# trigger.net
KiCad netlist of a schematic drawn in EAGLE
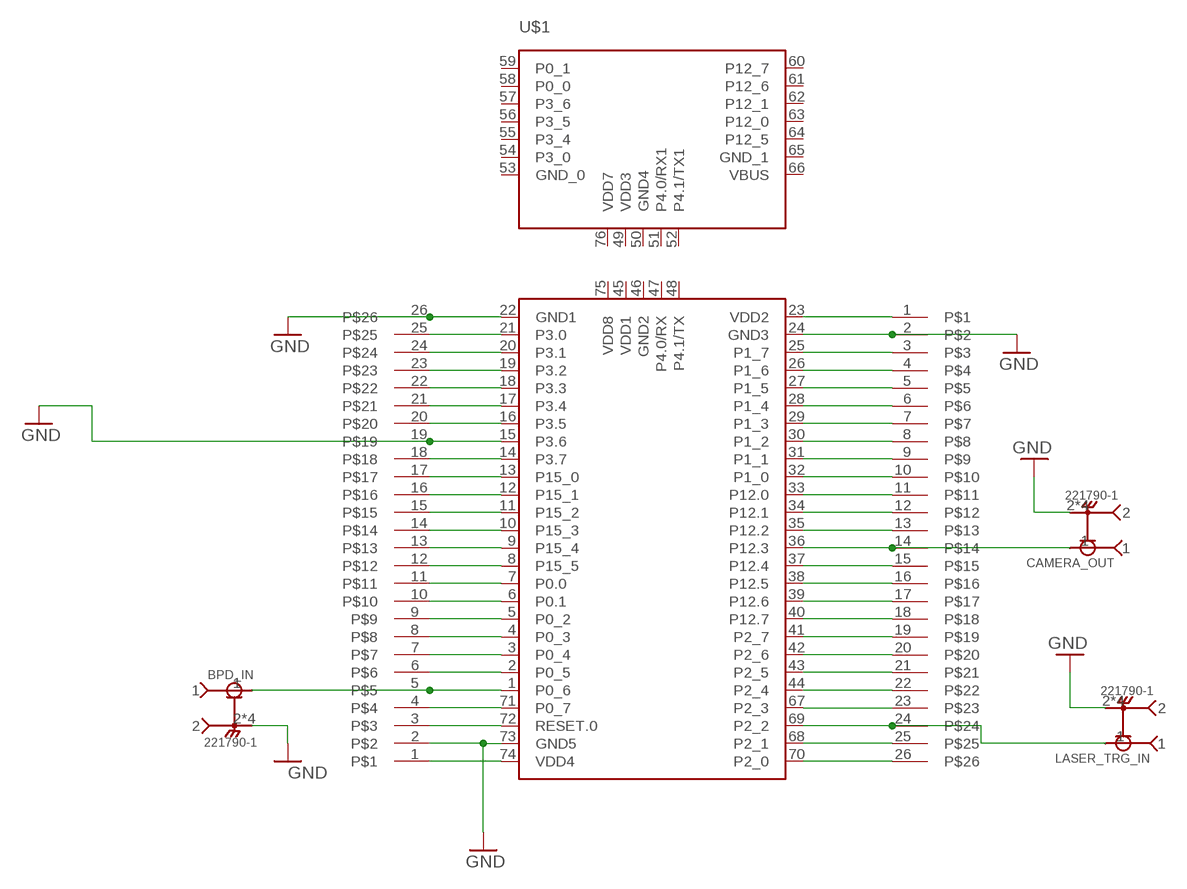
[diagram p0: schematic, sheet 1]

(export (version "E")
  (design (tool "Eeschema 10.0.6"))
  (components
    (comp (ref "BPD_IN")
      (value "221790-1")
      (footprint "eagle-import:TE_221790-1")
      (fields (field (name "MF") "TE Connectivity"))
      (libsource (lib "eagle-import") (part "221790-1"))
    )
    (comp (ref "CAMERA_OUT")
      (value "221790-1")
      (footprint "eagle-import:TE_221790-1")
      (fields (field (name "MF") "TE Connectivity"))
      (libsource (lib "eagle-import") (part "221790-1"))
    )
    (comp (ref "LASER_TRG_IN")
      (value "221790-1")
      (footprint "eagle-import:TE_221790-1")
      (fields (field (name "MF") "TE Connectivity"))
      (libsource (lib "eagle-import") (part "221790-1"))
    )
    (comp (ref "U$1")
      (value "CY8CKIT-049-42XX")
      (footprint "eagle-import:CY8CKIT-049-42XX")
      (fields (field (name "MF") "Cypress Semiconductor"))
      (libsource (lib "eagle-import") (part "CY8CKIT-049-42XX"))
    )
    (comp (ref "U$2")
      (value "PINHEADER_PSOC5LP")
      (footprint "eagle-import:PINHEADER")
      (libsource (lib "eagle-import") (part "PINHEADER_PSOC5LP"))
    )
    (comp (ref "U$3")
      (value "PINHEADER_PSOC5LP")
      (footprint "eagle-import:PINHEADER")
      (libsource (lib "eagle-import") (part "PINHEADER_PSOC5LP"))
    )
  )
  (nets
    (net (code "1") (name "GND") (class "Default")
      (node (ref "BPD_IN") (pin "2") (pinfunction "2_2") (pintype "passive"))
      (node (ref "BPD_IN") (pin "3") (pinfunction "2_3") (pintype "passive"))
      (node (ref "BPD_IN") (pin "4") (pinfunction "2_4") (pintype "passive"))
      (node (ref "BPD_IN") (pin "5") (pinfunction "2_5") (pintype "passive"))
      (node (ref "CAMERA_OUT") (pin "2") (pinfunction "2_2") (pintype "passive"))
      (node (ref "CAMERA_OUT") (pin "3") (pinfunction "2_3") (pintype "passive"))
      (node (ref "CAMERA_OUT") (pin "4") (pinfunction "2_4") (pintype "passive"))
      (node (ref "CAMERA_OUT") (pin "5") (pinfunction "2_5") (pintype "passive"))
      (node (ref "LASER_TRG_IN") (pin "2") (pinfunction "2_2") (pintype "passive"))
      (node (ref "LASER_TRG_IN") (pin "3") (pinfunction "2_3") (pintype "passive"))
      (node (ref "LASER_TRG_IN") (pin "4") (pinfunction "2_4") (pintype "passive"))
      (node (ref "LASER_TRG_IN") (pin "5") (pinfunction "2_5") (pintype "passive"))
      (node (ref "U$1") (pin "15") (pinfunction "P3.6_15") (pintype "bidirectional"))
      (node (ref "U$1") (pin "22") (pinfunction "GND1_22") (pintype "bidirectional"))
      (node (ref "U$1") (pin "24") (pinfunction "GND3_24") (pintype "bidirectional"))
      (node (ref "U$1") (pin "73") (pinfunction "GND5_73") (pintype "bidirectional"))
      (node (ref "U$2") (pin "19") (pinfunction "P$19_19") (pintype "bidirectional"))
      (node (ref "U$2") (pin "2") (pinfunction "P$2_2") (pintype "bidirectional"))
      (node (ref "U$2") (pin "26") (pinfunction "P$26_26") (pintype "bidirectional"))
      (node (ref "U$3") (pin "2") (pinfunction "P$2_2") (pintype "bidirectional"))
    )
    (net (code "2") (name "Net-(U$1-P0.0)") (class "Default")
      (node (ref "U$1") (pin "7") (pinfunction "P0.0_7") (pintype "bidirectional"))
      (node (ref "U$2") (pin "11") (pinfunction "P$11_11") (pintype "bidirectional"))
    )
    (net (code "3") (name "Net-(U$1-P0.1)") (class "Default")
      (node (ref "U$1") (pin "6") (pinfunction "P0.1_6") (pintype "bidirectional"))
      (node (ref "U$2") (pin "10") (pinfunction "P$10_10") (pintype "bidirectional"))
    )
    (net (code "4") (name "Net-(U$1-P0_2)") (class "Default")
      (node (ref "U$1") (pin "5") (pinfunction "P0_2_5") (pintype "bidirectional"))
      (node (ref "U$2") (pin "9") (pinfunction "P$9_9") (pintype "bidirectional"))
    )
    (net (code "5") (name "Net-(U$1-P0_3)") (class "Default")
      (node (ref "U$1") (pin "4") (pinfunction "P0_3_4") (pintype "bidirectional"))
      (node (ref "U$2") (pin "8") (pinfunction "P$8_8") (pintype "bidirectional"))
    )
    (net (code "6") (name "Net-(U$1-P0_4)") (class "Default")
      (node (ref "U$1") (pin "3") (pinfunction "P0_4_3") (pintype "bidirectional"))
      (node (ref "U$2") (pin "7") (pinfunction "P$7_7") (pintype "bidirectional"))
    )
    (net (code "7") (name "Net-(U$1-P0_5)") (class "Default")
      (node (ref "U$1") (pin "2") (pinfunction "P0_5_2") (pintype "bidirectional"))
      (node (ref "U$2") (pin "6") (pinfunction "P$6_6") (pintype "bidirectional"))
    )
    (net (code "8") (name "Net-(U$1-P0_6)") (class "Default")
      (node (ref "BPD_IN") (pin "1") (pinfunction "1_1") (pintype "passive"))
      (node (ref "U$1") (pin "1") (pinfunction "P0_6_1") (pintype "bidirectional"))
      (node (ref "U$2") (pin "5") (pinfunction "P$5_5") (pintype "bidirectional"))
    )
    (net (code "9") (name "Net-(U$1-P0_7)") (class "Default")
      (node (ref "U$1") (pin "71") (pinfunction "P0_7_71") (pintype "bidirectional"))
      (node (ref "U$2") (pin "4") (pinfunction "P$4_4") (pintype "bidirectional"))
    )
    (net (code "10") (name "Net-(U$1-P1_0)") (class "Default")
      (node (ref "U$1") (pin "32") (pinfunction "P1_0_32") (pintype "bidirectional"))
      (node (ref "U$3") (pin "10") (pinfunction "P$10_10") (pintype "bidirectional"))
    )
    (net (code "11") (name "Net-(U$1-P1_1)") (class "Default")
      (node (ref "U$1") (pin "31") (pinfunction "P1_1_31") (pintype "bidirectional"))
      (node (ref "U$3") (pin "9") (pinfunction "P$9_9") (pintype "bidirectional"))
    )
    (net (code "12") (name "Net-(U$1-P1_2)") (class "Default")
      (node (ref "U$1") (pin "30") (pinfunction "P1_2_30") (pintype "bidirectional"))
      (node (ref "U$3") (pin "8") (pinfunction "P$8_8") (pintype "bidirectional"))
    )
    (net (code "13") (name "Net-(U$1-P1_3)") (class "Default")
      (node (ref "U$1") (pin "29") (pinfunction "P1_3_29") (pintype "bidirectional"))
      (node (ref "U$3") (pin "7") (pinfunction "P$7_7") (pintype "bidirectional"))
    )
    (net (code "14") (name "Net-(U$1-P1_4)") (class "Default")
      (node (ref "U$1") (pin "28") (pinfunction "P1_4_28") (pintype "bidirectional"))
      (node (ref "U$3") (pin "6") (pinfunction "P$6_6") (pintype "bidirectional"))
    )
    (net (code "15") (name "Net-(U$1-P1_5)") (class "Default")
      (node (ref "U$1") (pin "27") (pinfunction "P1_5_27") (pintype "bidirectional"))
      (node (ref "U$3") (pin "5") (pinfunction "P$5_5") (pintype "bidirectional"))
    )
    (net (code "16") (name "Net-(U$1-P1_6)") (class "Default")
      (node (ref "U$1") (pin "26") (pinfunction "P1_6_26") (pintype "bidirectional"))
      (node (ref "U$3") (pin "4") (pinfunction "P$4_4") (pintype "bidirectional"))
    )
    (net (code "17") (name "Net-(U$1-P1_7)") (class "Default")
      (node (ref "U$1") (pin "25") (pinfunction "P1_7_25") (pintype "bidirectional"))
      (node (ref "U$3") (pin "3") (pinfunction "P$3_3") (pintype "bidirectional"))
    )
    (net (code "18") (name "Net-(U$1-P2_0)") (class "Default")
      (node (ref "U$1") (pin "70") (pinfunction "P2_0_70") (pintype "bidirectional"))
      (node (ref "U$3") (pin "26") (pinfunction "P$26_26") (pintype "bidirectional"))
    )
    (net (code "19") (name "Net-(U$1-P2_1)") (class "Default")
      (node (ref "U$1") (pin "68") (pinfunction "P2_1_68") (pintype "bidirectional"))
      (node (ref "U$3") (pin "25") (pinfunction "P$25_25") (pintype "bidirectional"))
    )
    (net (code "20") (name "Net-(U$1-P2_2)") (class "Default")
      (node (ref "LASER_TRG_IN") (pin "1") (pinfunction "1_1") (pintype "passive"))
      (node (ref "U$1") (pin "69") (pinfunction "P2_2_69") (pintype "bidirectional"))
      (node (ref "U$3") (pin "24") (pinfunction "P$24_24") (pintype "bidirectional"))
    )
    (net (code "21") (name "Net-(U$1-P2_3)") (class "Default")
      (node (ref "U$1") (pin "67") (pinfunction "P2_3_67") (pintype "bidirectional"))
      (node (ref "U$3") (pin "23") (pinfunction "P$23_23") (pintype "bidirectional"))
    )
    (net (code "22") (name "Net-(U$1-P2_4)") (class "Default")
      (node (ref "U$1") (pin "44") (pinfunction "P2_4_44") (pintype "bidirectional"))
      (node (ref "U$3") (pin "22") (pinfunction "P$22_22") (pintype "bidirectional"))
    )
    (net (code "23") (name "Net-(U$1-P2_5)") (class "Default")
      (node (ref "U$1") (pin "43") (pinfunction "P2_5_43") (pintype "bidirectional"))
      (node (ref "U$3") (pin "21") (pinfunction "P$21_21") (pintype "bidirectional"))
    )
    (net (code "24") (name "Net-(U$1-P2_6)") (class "Default")
      (node (ref "U$1") (pin "42") (pinfunction "P2_6_42") (pintype "bidirectional"))
      (node (ref "U$3") (pin "20") (pinfunction "P$20_20") (pintype "bidirectional"))
    )
    (net (code "25") (name "Net-(U$1-P2_7)") (class "Default")
      (node (ref "U$1") (pin "41") (pinfunction "P2_7_41") (pintype "bidirectional"))
      (node (ref "U$3") (pin "19") (pinfunction "P$19_19") (pintype "bidirectional"))
    )
    (net (code "26") (name "Net-(U$1-P3.0)") (class "Default")
      (node (ref "U$1") (pin "21") (pinfunction "P3.0_21") (pintype "bidirectional"))
      (node (ref "U$2") (pin "25") (pinfunction "P$25_25") (pintype "bidirectional"))
    )
    (net (code "27") (name "Net-(U$1-P3.1)") (class "Default")
      (node (ref "U$1") (pin "20") (pinfunction "P3.1_20") (pintype "bidirectional"))
      (node (ref "U$2") (pin "24") (pinfunction "P$24_24") (pintype "bidirectional"))
    )
    (net (code "28") (name "Net-(U$1-P3.2)") (class "Default")
      (node (ref "U$1") (pin "19") (pinfunction "P3.2_19") (pintype "bidirectional"))
      (node (ref "U$2") (pin "23") (pinfunction "P$23_23") (pintype "bidirectional"))
    )
    (net (code "29") (name "Net-(U$1-P3.3)") (class "Default")
      (node (ref "U$1") (pin "18") (pinfunction "P3.3_18") (pintype "bidirectional"))
      (node (ref "U$2") (pin "22") (pinfunction "P$22_22") (pintype "bidirectional"))
    )
    (net (code "30") (name "Net-(U$1-P3.4)") (class "Default")
      (node (ref "U$1") (pin "17") (pinfunction "P3.4_17") (pintype "bidirectional"))
      (node (ref "U$2") (pin "21") (pinfunction "P$21_21") (pintype "bidirectional"))
    )
    (net (code "31") (name "Net-(U$1-P3.5)") (class "Default")
      (node (ref "U$1") (pin "16") (pinfunction "P3.5_16") (pintype "bidirectional"))
      (node (ref "U$2") (pin "20") (pinfunction "P$20_20") (pintype "bidirectional"))
    )
    (net (code "32") (name "Net-(U$1-P3.7)") (class "Default")
      (node (ref "U$1") (pin "14") (pinfunction "P3.7_14") (pintype "bidirectional"))
      (node (ref "U$2") (pin "18") (pinfunction "P$18_18") (pintype "bidirectional"))
    )
    (net (code "33") (name "Net-(U$1-P12.0)") (class "Default")
      (node (ref "U$1") (pin "33") (pinfunction "P12.0_33") (pintype "bidirectional"))
      (node (ref "U$3") (pin "11") (pinfunction "P$11_11") (pintype "bidirectional"))
    )
    (net (code "34") (name "Net-(U$1-P12.1)") (class "Default")
      (node (ref "U$1") (pin "34") (pinfunction "P12.1_34") (pintype "bidirectional"))
      (node (ref "U$3") (pin "12") (pinfunction "P$12_12") (pintype "bidirectional"))
    )
    (net (code "35") (name "Net-(U$1-P12.2)") (class "Default")
      (node (ref "U$1") (pin "35") (pinfunction "P12.2_35") (pintype "bidirectional"))
      (node (ref "U$3") (pin "13") (pinfunction "P$13_13") (pintype "bidirectional"))
    )
    (net (code "36") (name "Net-(U$1-P12.3)") (class "Default")
      (node (ref "CAMERA_OUT") (pin "1") (pinfunction "1_1") (pintype "passive"))
      (node (ref "U$1") (pin "36") (pinfunction "P12.3_36") (pintype "bidirectional"))
      (node (ref "U$3") (pin "14") (pinfunction "P$14_14") (pintype "bidirectional"))
    )
    (net (code "37") (name "Net-(U$1-P12.4)") (class "Default")
      (node (ref "U$1") (pin "37") (pinfunction "P12.4_37") (pintype "bidirectional"))
      (node (ref "U$3") (pin "15") (pinfunction "P$15_15") (pintype "bidirectional"))
    )
    (net (code "38") (name "Net-(U$1-P12.5)") (class "Default")
      (node (ref "U$1") (pin "38") (pinfunction "P12.5_38") (pintype "bidirectional"))
      (node (ref "U$3") (pin "16") (pinfunction "P$16_16") (pintype "bidirectional"))
    )
    (net (code "39") (name "Net-(U$1-P12.6)") (class "Default")
      (node (ref "U$1") (pin "39") (pinfunction "P12.6_39") (pintype "bidirectional"))
      (node (ref "U$3") (pin "17") (pinfunction "P$17_17") (pintype "bidirectional"))
    )
    (net (code "40") (name "Net-(U$1-P12.7)") (class "Default")
      (node (ref "U$1") (pin "40") (pinfunction "P12.7_40") (pintype "bidirectional"))
      (node (ref "U$3") (pin "18") (pinfunction "P$18_18") (pintype "bidirectional"))
    )
    (net (code "41") (name "Net-(U$1-P15_0)") (class "Default")
      (node (ref "U$1") (pin "13") (pinfunction "P15_0_13") (pintype "bidirectional"))
      (node (ref "U$2") (pin "17") (pinfunction "P$17_17") (pintype "bidirectional"))
    )
    (net (code "42") (name "Net-(U$1-P15_1)") (class "Default")
      (node (ref "U$1") (pin "12") (pinfunction "P15_1_12") (pintype "bidirectional"))
      (node (ref "U$2") (pin "16") (pinfunction "P$16_16") (pintype "bidirectional"))
    )
    (net (code "43") (name "Net-(U$1-P15_2)") (class "Default")
      (node (ref "U$1") (pin "11") (pinfunction "P15_2_11") (pintype "bidirectional"))
      (node (ref "U$2") (pin "15") (pinfunction "P$15_15") (pintype "bidirectional"))
    )
    (net (code "44") (name "Net-(U$1-P15_3)") (class "Default")
      (node (ref "U$1") (pin "10") (pinfunction "P15_3_10") (pintype "bidirectional"))
      (node (ref "U$2") (pin "14") (pinfunction "P$14_14") (pintype "bidirectional"))
    )
    (net (code "45") (name "Net-(U$1-P15_4)") (class "Default")
      (node (ref "U$1") (pin "9") (pinfunction "P15_4_9") (pintype "bidirectional"))
      (node (ref "U$2") (pin "13") (pinfunction "P$13_13") (pintype "bidirectional"))
    )
    (net (code "46") (name "Net-(U$1-P15_5)") (class "Default")
      (node (ref "U$1") (pin "8") (pinfunction "P15_5_8") (pintype "bidirectional"))
      (node (ref "U$2") (pin "12") (pinfunction "P$12_12") (pintype "bidirectional"))
    )
    (net (code "47") (name "Net-(U$1-RESET.0)") (class "Default")
      (node (ref "U$1") (pin "72") (pinfunction "RESET.0_72") (pintype "bidirectional"))
      (node (ref "U$2") (pin "3") (pinfunction "P$3_3") (pintype "bidirectional"))
    )
    (net (code "48") (name "Net-(U$1-VDD2)") (class "Default")
      (node (ref "U$1") (pin "23") (pinfunction "VDD2_23") (pintype "bidirectional"))
      (node (ref "U$3") (pin "1") (pinfunction "P$1_1") (pintype "bidirectional"))
    )
    (net (code "49") (name "Net-(U$1-VDD4)") (class "Default")
      (node (ref "U$1") (pin "74") (pinfunction "VDD4_74") (pintype "bidirectional"))
      (node (ref "U$2") (pin "1") (pinfunction "P$1_1") (pintype "bidirectional"))
    )
    (net (code "50") (name "unconnected-(U$1-GND2-Pad46)") (class "Default")
      (node (ref "U$1") (pin "46") (pinfunction "GND2_46") (pintype "bidirectional"))
    )
    (net (code "51") (name "unconnected-(U$1-GND4-Pad50)") (class "Default")
      (node (ref "U$1") (pin "50") (pinfunction "GND4_50") (pintype "bidirectional"))
    )
    (net (code "52") (name "unconnected-(U$1-GND_0-Pad53)") (class "Default")
      (node (ref "U$1") (pin "53") (pinfunction "GND_0_53") (pintype "bidirectional"))
    )
    (net (code "53") (name "unconnected-(U$1-GND_1-Pad65)") (class "Default")
      (node (ref "U$1") (pin "65") (pinfunction "GND_1_65") (pintype "bidirectional"))
    )
    (net (code "54") (name "unconnected-(U$1-P0_0-Pad58)") (class "Default")
      (node (ref "U$1") (pin "58") (pinfunction "P0_0_58") (pintype "bidirectional"))
    )
    (net (code "55") (name "unconnected-(U$1-P0_1-Pad59)") (class "Default")
      (node (ref "U$1") (pin "59") (pinfunction "P0_1_59") (pintype "bidirectional"))
    )
    (net (code "56") (name "unconnected-(U$1-P3_0-Pad54)") (class "Default")
      (node (ref "U$1") (pin "54") (pinfunction "P3_0_54") (pintype "bidirectional"))
    )
    (net (code "57") (name "unconnected-(U$1-P3_4-Pad55)") (class "Default")
      (node (ref "U$1") (pin "55") (pinfunction "P3_4_55") (pintype "bidirectional"))
    )
    (net (code "58") (name "unconnected-(U$1-P3_5-Pad56)") (class "Default")
      (node (ref "U$1") (pin "56") (pinfunction "P3_5_56") (pintype "bidirectional"))
    )
    (net (code "59") (name "unconnected-(U$1-P3_6-Pad57)") (class "Default")
      (node (ref "U$1") (pin "57") (pinfunction "P3_6_57") (pintype "bidirectional"))
    )
    (net (code "60") (name "unconnected-(U$1-P4.0{slash}RX-Pad47)") (class "Default")
      (node (ref "U$1") (pin "47") (pinfunction "P4.0/RX_47") (pintype "bidirectional"))
    )
    (net (code "61") (name "unconnected-(U$1-P4.0{slash}RX1-Pad51)") (class "Default")
      (node (ref "U$1") (pin "51") (pinfunction "P4.0/RX1_51") (pintype "bidirectional"))
    )
    (net (code "62") (name "unconnected-(U$1-P4.1{slash}TX-Pad48)") (class "Default")
      (node (ref "U$1") (pin "48") (pinfunction "P4.1/TX_48") (pintype "bidirectional"))
    )
    (net (code "63") (name "unconnected-(U$1-P4.1{slash}TX1-Pad52)") (class "Default")
      (node (ref "U$1") (pin "52") (pinfunction "P4.1/TX1_52") (pintype "bidirectional"))
    )
    (net (code "64") (name "unconnected-(U$1-P12_0-Pad63)") (class "Default")
      (node (ref "U$1") (pin "63") (pinfunction "P12_0_63") (pintype "bidirectional"))
    )
    (net (code "65") (name "unconnected-(U$1-P12_1-Pad62)") (class "Default")
      (node (ref "U$1") (pin "62") (pinfunction "P12_1_62") (pintype "bidirectional"))
    )
    (net (code "66") (name "unconnected-(U$1-P12_5-Pad64)") (class "Default")
      (node (ref "U$1") (pin "64") (pinfunction "P12_5_64") (pintype "bidirectional"))
    )
    (net (code "67") (name "unconnected-(U$1-P12_6-Pad61)") (class "Default")
      (node (ref "U$1") (pin "61") (pinfunction "P12_6_61") (pintype "bidirectional"))
    )
    (net (code "68") (name "unconnected-(U$1-P12_7-Pad60)") (class "Default")
      (node (ref "U$1") (pin "60") (pinfunction "P12_7_60") (pintype "bidirectional"))
    )
    (net (code "69") (name "unconnected-(U$1-VBUS-Pad66)") (class "Default")
      (node (ref "U$1") (pin "66") (pinfunction "VBUS_66") (pintype "bidirectional"))
    )
    (net (code "70") (name "unconnected-(U$1-VDD1-Pad45)") (class "Default")
      (node (ref "U$1") (pin "45") (pinfunction "VDD1_45") (pintype "bidirectional"))
    )
    (net (code "71") (name "unconnected-(U$1-VDD3-Pad49)") (class "Default")
      (node (ref "U$1") (pin "49") (pinfunction "VDD3_49") (pintype "bidirectional"))
    )
    (net (code "72") (name "unconnected-(U$1-VDD7-Pad76)") (class "Default")
      (node (ref "U$1") (pin "76") (pinfunction "VDD7_76") (pintype "bidirectional"))
    )
    (net (code "73") (name "unconnected-(U$1-VDD8-Pad75)") (class "Default")
      (node (ref "U$1") (pin "75") (pinfunction "VDD8_75") (pintype "bidirectional"))
    )
  )
)
